# CatNode.net
KiCad netlist of a schematic drawn in EAGLE
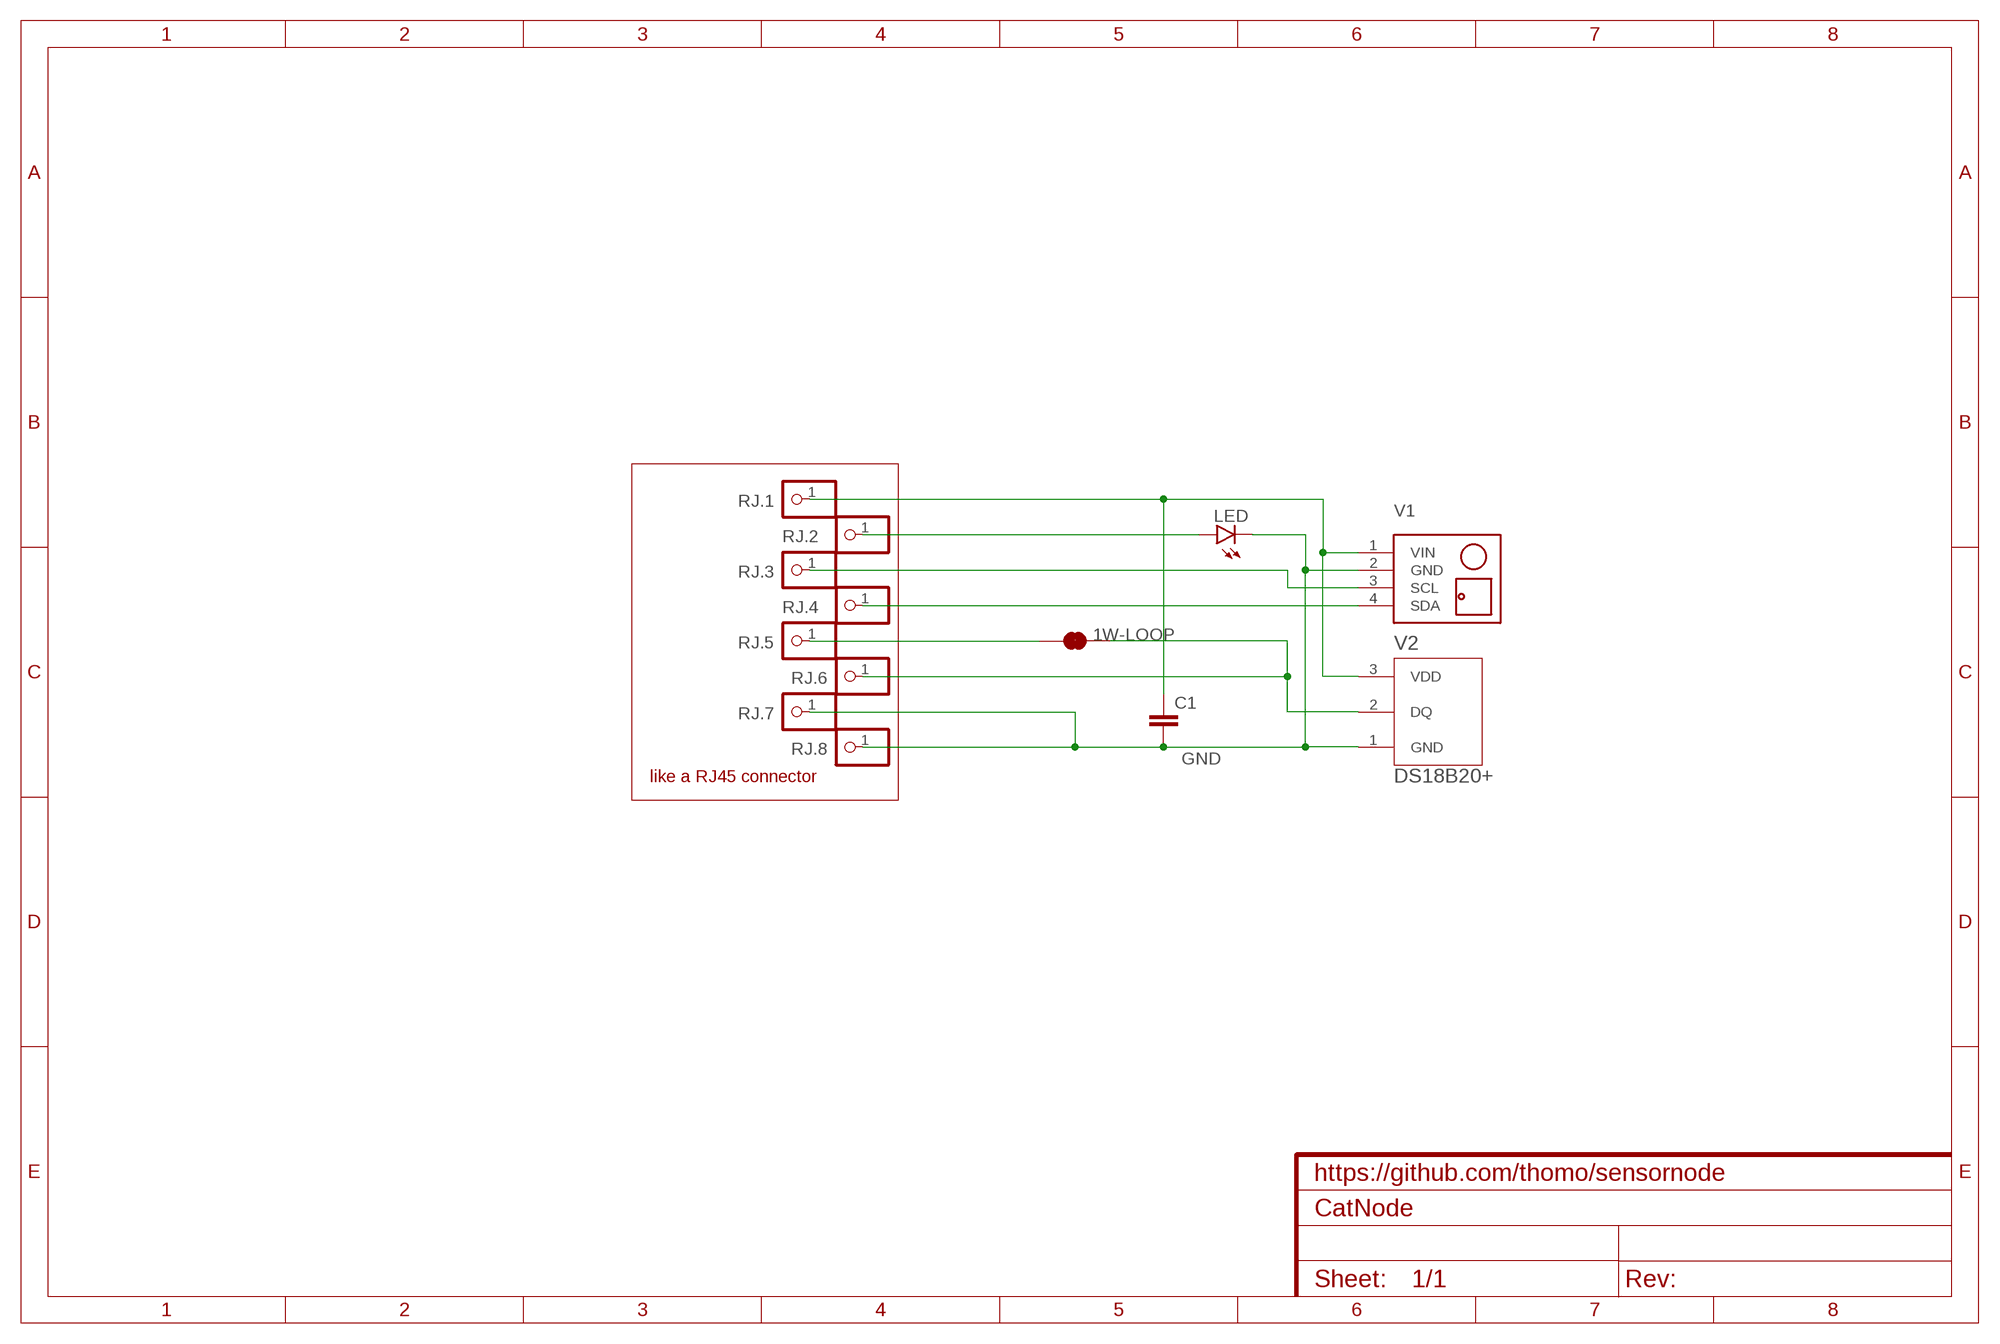
[diagram p0: schematic, sheet 1]

(export (version "E")
  (design (tool "Eeschema 10.0.6"))
  (components
    (comp (ref "1W-LOOP")
      (value "JUMPER-SMT_2_NC_TRACE_SILK")
      (footprint "eagle-import:SMT-JUMPER_2_NC_TRACE_SILK")
      (libsource (lib "eagle-import") (part "JUMPER-SMT_2_NC_TRACE_SILK"))
    )
    (comp (ref "C1")
      (value "C-EUC0805")
      (footprint "eagle-import:C0805")
      (libsource (lib "eagle-import") (part "C-EUC0805"))
    )
    (comp (ref "LED")
      (value "LEDSML0805")
      (footprint "eagle-import:SML0805")
      (libsource (lib "eagle-import") (part "LEDSML0805"))
    )
    (comp (ref "RJ.1")
      (value "PINHD-1X1")
      (footprint "eagle-import:1X01")
      (libsource (lib "eagle-import") (part "PINHD-1X1"))
    )
    (comp (ref "RJ.2")
      (value "PINHD-1X1")
      (footprint "eagle-import:1X01")
      (libsource (lib "eagle-import") (part "PINHD-1X1"))
    )
    (comp (ref "RJ.3")
      (value "PINHD-1X1")
      (footprint "eagle-import:1X01")
      (libsource (lib "eagle-import") (part "PINHD-1X1"))
    )
    (comp (ref "RJ.4")
      (value "PINHD-1X1")
      (footprint "eagle-import:1X01")
      (libsource (lib "eagle-import") (part "PINHD-1X1"))
    )
    (comp (ref "RJ.5")
      (value "PINHD-1X1")
      (footprint "eagle-import:1X01")
      (libsource (lib "eagle-import") (part "PINHD-1X1"))
    )
    (comp (ref "RJ.6")
      (value "PINHD-1X1")
      (footprint "eagle-import:1X01")
      (libsource (lib "eagle-import") (part "PINHD-1X1"))
    )
    (comp (ref "RJ.7")
      (value "PINHD-1X1")
      (footprint "eagle-import:1X01")
      (libsource (lib "eagle-import") (part "PINHD-1X1"))
    )
    (comp (ref "RJ.8")
      (value "PINHD-1X1")
      (footprint "eagle-import:1X01")
      (libsource (lib "eagle-import") (part "PINHD-1X1"))
    )
    (comp (ref "V1")
      (value "TEMP-HUM-PRES-BME280")
      (footprint "eagle-import:TEMP-HUM-PRES-BME280")
      (libsource (lib "eagle-import") (part "TEMP-HUM-PRES-BME280"))
    )
    (comp (ref "V2")
      (value "DS18B20+")
      (footprint "eagle-import:TO-92")
      (libsource (lib "eagle-import") (part "DS18B20+"))
    )
  )
  (nets
    (net (code "1") (name "/GND") (class "Default")
      (node (ref "C1") (pin "2") (pinfunction "2_2") (pintype "passive"))
      (node (ref "LED") (pin "C") (pinfunction "C_C") (pintype "passive"))
      (node (ref "RJ.7") (pin "1") (pinfunction "1_1") (pintype "passive"))
      (node (ref "RJ.8") (pin "1") (pinfunction "1_1") (pintype "passive"))
      (node (ref "V1") (pin "2") (pinfunction "GND_2") (pintype "power_in"))
      (node (ref "V2") (pin "1") (pinfunction "GND_1") (pintype "power_in"))
    )
    (net (code "2") (name "Net-(1W-LOOP-Pad1)") (class "Default")
      (node (ref "1W-LOOP") (pin "1") (pinfunction "1_1") (pintype "passive"))
      (node (ref "RJ.5") (pin "1") (pinfunction "1_1") (pintype "passive"))
    )
    (net (code "3") (name "Net-(LED-PadA)") (class "Default")
      (node (ref "LED") (pin "A") (pinfunction "A_A") (pintype "passive"))
      (node (ref "RJ.2") (pin "1") (pinfunction "1_1") (pintype "passive"))
    )
    (net (code "4") (name "Net-(V1-SCL)") (class "Default")
      (node (ref "RJ.3") (pin "1") (pinfunction "1_1") (pintype "passive"))
      (node (ref "V1") (pin "3") (pinfunction "SCL_3") (pintype "bidirectional"))
    )
    (net (code "5") (name "Net-(V1-SDA)") (class "Default")
      (node (ref "RJ.4") (pin "1") (pinfunction "1_1") (pintype "passive"))
      (node (ref "V1") (pin "4") (pinfunction "SDA_4") (pintype "bidirectional"))
    )
    (net (code "6") (name "Net-(V1-VIN)") (class "Default")
      (node (ref "C1") (pin "1") (pinfunction "1_1") (pintype "passive"))
      (node (ref "RJ.1") (pin "1") (pinfunction "1_1") (pintype "passive"))
      (node (ref "V1") (pin "1") (pinfunction "VIN_1") (pintype "power_in"))
      (node (ref "V2") (pin "3") (pinfunction "VDD_3") (pintype "power_in"))
    )
    (net (code "7") (name "Net-(V2-DQ)") (class "Default")
      (node (ref "1W-LOOP") (pin "2") (pinfunction "2_2") (pintype "passive"))
      (node (ref "RJ.6") (pin "1") (pinfunction "1_1") (pintype "passive"))
      (node (ref "V2") (pin "2") (pinfunction "DQ_2") (pintype "bidirectional"))
    )
  )
)
